# UI_Adapter_SMD.net
KiCad netlist of a schematic drawn in EAGLE
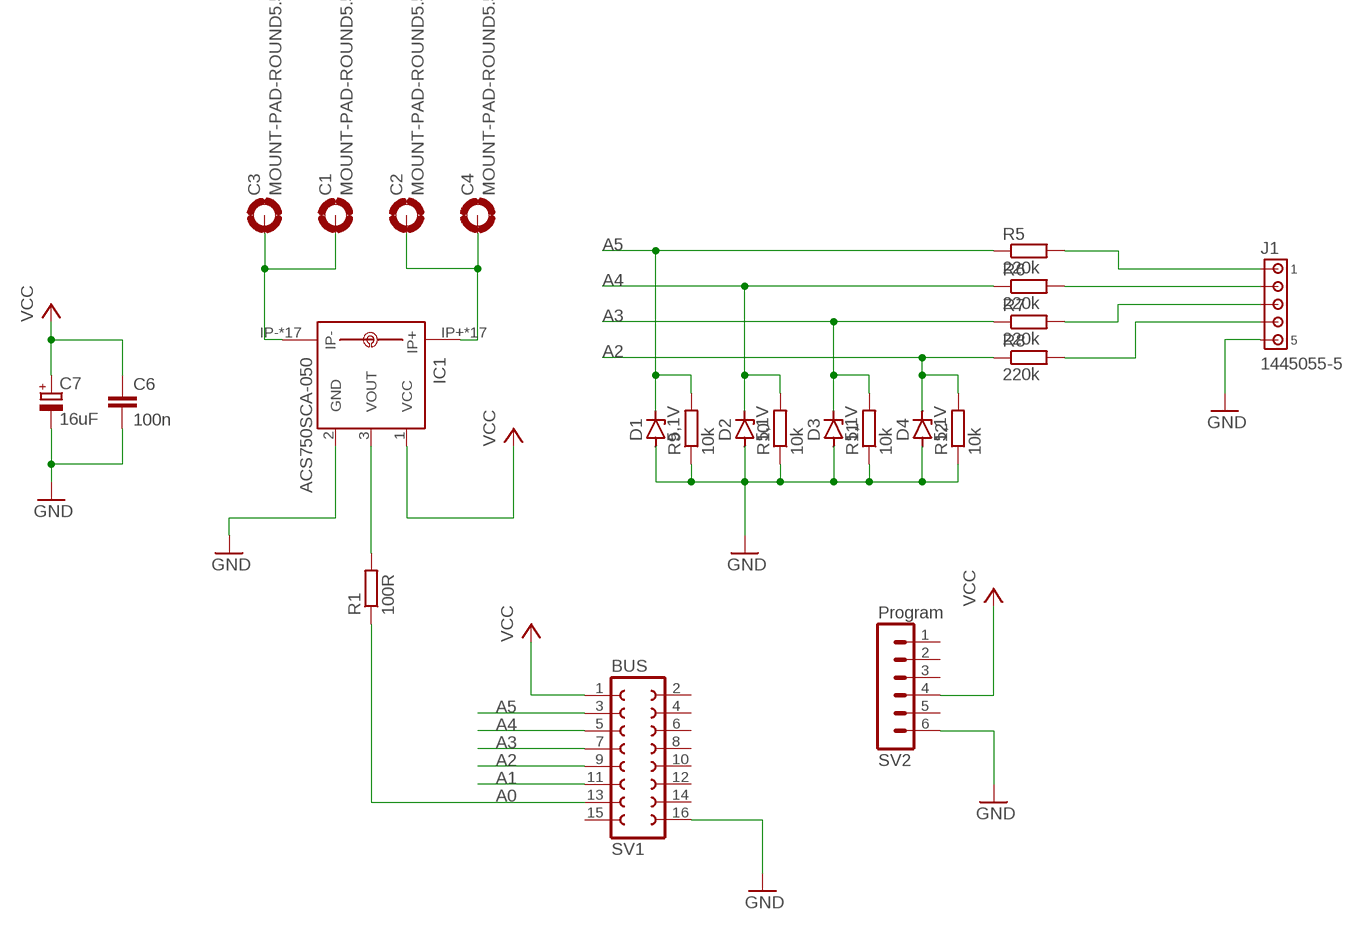
[diagram p0: schematic, sheet 1]

(export (version "E")
  (design (tool "Eeschema 10.0.6"))
  (components
    (comp (ref "C1")
      (value "MOUNT-PAD-ROUND5.5")
      (footprint "eagle-import:5,5-PAD")
      (libsource (lib "eagle-import") (part "MOUNT-PAD-ROUND5.5"))
    )
    (comp (ref "C2")
      (value "MOUNT-PAD-ROUND5.5")
      (footprint "eagle-import:5,5-PAD")
      (libsource (lib "eagle-import") (part "MOUNT-PAD-ROUND5.5"))
    )
    (comp (ref "C3")
      (value "MOUNT-PAD-ROUND5.5")
      (footprint "eagle-import:5,5-PAD")
      (libsource (lib "eagle-import") (part "MOUNT-PAD-ROUND5.5"))
    )
    (comp (ref "C4")
      (value "MOUNT-PAD-ROUND5.5")
      (footprint "eagle-import:5,5-PAD")
      (libsource (lib "eagle-import") (part "MOUNT-PAD-ROUND5.5"))
    )
    (comp (ref "C6")
      (value "100n")
      (footprint "eagle-import:C0402K")
      (libsource (lib "eagle-import") (part "C-EUC0402K"))
    )
    (comp (ref "C7")
      (value "16uF")
      (footprint "eagle-import:A_3216-18W")
      (libsource (lib "eagle-import") (part "CPOL-EUA/3216-18W"))
    )
    (comp (ref "D1")
      (value "5,1V")
      (footprint "eagle-import:SOD80C")
      (libsource (lib "eagle-import") (part "ZENER-DIODESOD80C"))
    )
    (comp (ref "D2")
      (value "5,1V")
      (footprint "eagle-import:SOD80C")
      (libsource (lib "eagle-import") (part "ZENER-DIODESOD80C"))
    )
    (comp (ref "D3")
      (value "5,1V")
      (footprint "eagle-import:SOD80C")
      (libsource (lib "eagle-import") (part "ZENER-DIODESOD80C"))
    )
    (comp (ref "D4")
      (value "5,1V")
      (footprint "eagle-import:SOD80C")
      (libsource (lib "eagle-import") (part "ZENER-DIODESOD80C"))
    )
    (comp (ref "IC1")
      (value "ACS750SCA-050")
      (footprint "eagle-import:ACS75050")
      (fields (field (name "MF") "ALLEGRO MICROSYSTEMS, INC."))
      (libsource (lib "eagle-import") (part "ACS750CA-050S"))
    )
    (comp (ref "J1")
      (value "1445055-5")
      (footprint "eagle-import:1445055-5")
      (libsource (lib "eagle-import") (part "1445055-5"))
    )
    (comp (ref "R1")
      (value "100R")
      (footprint "eagle-import:R0402")
      (libsource (lib "eagle-import") (part "R-EU_R0402"))
    )
    (comp (ref "R5")
      (value "220k")
      (footprint "eagle-import:R0402")
      (libsource (lib "eagle-import") (part "R-EU_R0402"))
    )
    (comp (ref "R6")
      (value "220k")
      (footprint "eagle-import:R0402")
      (libsource (lib "eagle-import") (part "R-EU_R0402"))
    )
    (comp (ref "R7")
      (value "220k")
      (footprint "eagle-import:R0402")
      (libsource (lib "eagle-import") (part "R-EU_R0402"))
    )
    (comp (ref "R8")
      (value "220k")
      (footprint "eagle-import:R0402")
      (libsource (lib "eagle-import") (part "R-EU_R0402"))
    )
    (comp (ref "R9")
      (value "10k")
      (footprint "eagle-import:R0402")
      (libsource (lib "eagle-import") (part "R-EU_R0402"))
    )
    (comp (ref "R10")
      (value "10k")
      (footprint "eagle-import:R0402")
      (libsource (lib "eagle-import") (part "R-EU_R0402"))
    )
    (comp (ref "R11")
      (value "10k")
      (footprint "eagle-import:R0402")
      (libsource (lib "eagle-import") (part "R-EU_R0402"))
    )
    (comp (ref "R12")
      (value "10k")
      (footprint "eagle-import:R0402")
      (libsource (lib "eagle-import") (part "R-EU_R0402"))
    )
    (comp (ref "SV1")
      (value "BUS")
      (footprint "eagle-import:FE08-2")
      (libsource (lib "eagle-import") (part "FE08-2"))
    )
    (comp (ref "SV2")
      (value "Program")
      (footprint "eagle-import:MA06-1")
      (libsource (lib "eagle-import") (part "MA06-1"))
    )
  )
  (nets
    (net (code "1") (name "A0") (class "Default")
      (node (ref "R1") (pin "1") (pinfunction "1_1") (pintype "passive"))
      (node (ref "SV1") (pin "13") (pinfunction "13_13") (pintype "passive"))
    )
    (net (code "2") (name "A1") (class "Default")
      (node (ref "SV1") (pin "11") (pinfunction "11_11") (pintype "passive"))
    )
    (net (code "3") (name "A2") (class "Default")
      (node (ref "D4") (pin "C") (pinfunction "C_C") (pintype "passive"))
      (node (ref "R12") (pin "2") (pinfunction "2_2") (pintype "passive"))
      (node (ref "R8") (pin "1") (pinfunction "1_1") (pintype "passive"))
      (node (ref "SV1") (pin "9") (pinfunction "9_9") (pintype "passive"))
    )
    (net (code "4") (name "A3") (class "Default")
      (node (ref "D3") (pin "C") (pinfunction "C_C") (pintype "passive"))
      (node (ref "R11") (pin "2") (pinfunction "2_2") (pintype "passive"))
      (node (ref "R7") (pin "1") (pinfunction "1_1") (pintype "passive"))
      (node (ref "SV1") (pin "7") (pinfunction "7_7") (pintype "passive"))
    )
    (net (code "5") (name "A4") (class "Default")
      (node (ref "D2") (pin "C") (pinfunction "C_C") (pintype "passive"))
      (node (ref "R10") (pin "2") (pinfunction "2_2") (pintype "passive"))
      (node (ref "R6") (pin "1") (pinfunction "1_1") (pintype "passive"))
      (node (ref "SV1") (pin "5") (pinfunction "5_5") (pintype "passive"))
    )
    (net (code "6") (name "A5") (class "Default")
      (node (ref "D1") (pin "C") (pinfunction "C_C") (pintype "passive"))
      (node (ref "R5") (pin "1") (pinfunction "1_1") (pintype "passive"))
      (node (ref "R9") (pin "2") (pinfunction "2_2") (pintype "passive"))
      (node (ref "SV1") (pin "3") (pinfunction "3_3") (pintype "passive"))
    )
    (net (code "7") (name "GND") (class "Default")
      (node (ref "C6") (pin "2") (pinfunction "2_2") (pintype "passive"))
      (node (ref "C7") (pin "-") (pinfunction "-_-") (pintype "passive"))
      (node (ref "D1") (pin "A") (pinfunction "A_A") (pintype "passive"))
      (node (ref "D2") (pin "A") (pinfunction "A_A") (pintype "passive"))
      (node (ref "D3") (pin "A") (pinfunction "A_A") (pintype "passive"))
      (node (ref "D4") (pin "A") (pinfunction "A_A") (pintype "passive"))
      (node (ref "IC1") (pin "2") (pinfunction "GND_2") (pintype "power_in"))
      (node (ref "J1") (pin "5") (pinfunction "5_5") (pintype "passive"))
      (node (ref "R10") (pin "1") (pinfunction "1_1") (pintype "passive"))
      (node (ref "R11") (pin "1") (pinfunction "1_1") (pintype "passive"))
      (node (ref "R12") (pin "1") (pinfunction "1_1") (pintype "passive"))
      (node (ref "R9") (pin "1") (pinfunction "1_1") (pintype "passive"))
      (node (ref "SV1") (pin "16") (pinfunction "16_16") (pintype "passive"))
      (node (ref "SV2") (pin "6") (pinfunction "6_6") (pintype "passive"))
    )
    (net (code "8") (name "Net-(C1-MOUNT)") (class "Default")
      (node (ref "C1") (pin "B5,5") (pinfunction "MOUNT_B5,5") (pintype "passive"))
      (node (ref "C3") (pin "B5,5") (pinfunction "MOUNT_B5,5") (pintype "passive"))
      (node (ref "IC1") (pin "IP-") (pinfunction "IP-_IP-") (pintype "passive"))
      (node (ref "IC1") (pin "IP-@10") (pinfunction "IP-_IP-@10") (pintype "passive"))
      (node (ref "IC1") (pin "IP-@11") (pinfunction "IP-_IP-@11") (pintype "passive"))
      (node (ref "IC1") (pin "IP-@12") (pinfunction "IP-_IP-@12") (pintype "passive"))
      (node (ref "IC1") (pin "IP-@13") (pinfunction "IP-_IP-@13") (pintype "passive"))
      (node (ref "IC1") (pin "IP-@14") (pinfunction "IP-_IP-@14") (pintype "passive"))
      (node (ref "IC1") (pin "IP-@15") (pinfunction "IP-_IP-@15") (pintype "passive"))
      (node (ref "IC1") (pin "IP-@16") (pinfunction "IP-_IP-@16") (pintype "passive"))
      (node (ref "IC1") (pin "IP-@17") (pinfunction "IP-_IP-@17") (pintype "passive"))
      (node (ref "IC1") (pin "IP-@2") (pinfunction "IP-_IP-@2") (pintype "passive"))
      (node (ref "IC1") (pin "IP-@3") (pinfunction "IP-_IP-@3") (pintype "passive"))
      (node (ref "IC1") (pin "IP-@4") (pinfunction "IP-_IP-@4") (pintype "passive"))
      (node (ref "IC1") (pin "IP-@5") (pinfunction "IP-_IP-@5") (pintype "passive"))
      (node (ref "IC1") (pin "IP-@6") (pinfunction "IP-_IP-@6") (pintype "passive"))
      (node (ref "IC1") (pin "IP-@7") (pinfunction "IP-_IP-@7") (pintype "passive"))
      (node (ref "IC1") (pin "IP-@8") (pinfunction "IP-_IP-@8") (pintype "passive"))
      (node (ref "IC1") (pin "IP-@9") (pinfunction "IP-_IP-@9") (pintype "passive"))
    )
    (net (code "9") (name "Net-(C2-MOUNT)") (class "Default")
      (node (ref "C2") (pin "B5,5") (pinfunction "MOUNT_B5,5") (pintype "passive"))
      (node (ref "C4") (pin "B5,5") (pinfunction "MOUNT_B5,5") (pintype "passive"))
      (node (ref "IC1") (pin "IP+") (pinfunction "IP+_IP+") (pintype "passive"))
      (node (ref "IC1") (pin "IP+@10") (pinfunction "IP+_IP+@10") (pintype "passive"))
      (node (ref "IC1") (pin "IP+@11") (pinfunction "IP+_IP+@11") (pintype "passive"))
      (node (ref "IC1") (pin "IP+@12") (pinfunction "IP+_IP+@12") (pintype "passive"))
      (node (ref "IC1") (pin "IP+@13") (pinfunction "IP+_IP+@13") (pintype "passive"))
      (node (ref "IC1") (pin "IP+@14") (pinfunction "IP+_IP+@14") (pintype "passive"))
      (node (ref "IC1") (pin "IP+@15") (pinfunction "IP+_IP+@15") (pintype "passive"))
      (node (ref "IC1") (pin "IP+@16") (pinfunction "IP+_IP+@16") (pintype "passive"))
      (node (ref "IC1") (pin "IP+@17") (pinfunction "IP+_IP+@17") (pintype "passive"))
      (node (ref "IC1") (pin "IP+@2") (pinfunction "IP+_IP+@2") (pintype "passive"))
      (node (ref "IC1") (pin "IP+@3") (pinfunction "IP+_IP+@3") (pintype "passive"))
      (node (ref "IC1") (pin "IP+@4") (pinfunction "IP+_IP+@4") (pintype "passive"))
      (node (ref "IC1") (pin "IP+@5") (pinfunction "IP+_IP+@5") (pintype "passive"))
      (node (ref "IC1") (pin "IP+@6") (pinfunction "IP+_IP+@6") (pintype "passive"))
      (node (ref "IC1") (pin "IP+@7") (pinfunction "IP+_IP+@7") (pintype "passive"))
      (node (ref "IC1") (pin "IP+@8") (pinfunction "IP+_IP+@8") (pintype "passive"))
      (node (ref "IC1") (pin "IP+@9") (pinfunction "IP+_IP+@9") (pintype "passive"))
    )
    (net (code "10") (name "Net-(IC1-VOUT)") (class "Default")
      (node (ref "IC1") (pin "3") (pinfunction "VOUT_3") (pintype "output"))
      (node (ref "R1") (pin "2") (pinfunction "2_2") (pintype "passive"))
    )
    (net (code "11") (name "Net-(J1-Pad1)") (class "Default")
      (node (ref "J1") (pin "1") (pinfunction "1_1") (pintype "passive"))
      (node (ref "R5") (pin "2") (pinfunction "2_2") (pintype "passive"))
    )
    (net (code "12") (name "Net-(J1-Pad2)") (class "Default")
      (node (ref "J1") (pin "2") (pinfunction "2_2") (pintype "passive"))
      (node (ref "R6") (pin "2") (pinfunction "2_2") (pintype "passive"))
    )
    (net (code "13") (name "Net-(J1-Pad3)") (class "Default")
      (node (ref "J1") (pin "3") (pinfunction "3_3") (pintype "passive"))
      (node (ref "R7") (pin "2") (pinfunction "2_2") (pintype "passive"))
    )
    (net (code "14") (name "Net-(J1-Pad4)") (class "Default")
      (node (ref "J1") (pin "4") (pinfunction "4_4") (pintype "passive"))
      (node (ref "R8") (pin "2") (pinfunction "2_2") (pintype "passive"))
    )
    (net (code "15") (name "VCC") (class "Default")
      (node (ref "C6") (pin "1") (pinfunction "1_1") (pintype "passive"))
      (node (ref "C7") (pin "+") (pinfunction "+_+") (pintype "passive"))
      (node (ref "IC1") (pin "1") (pinfunction "VCC_1") (pintype "power_in"))
      (node (ref "SV1") (pin "1") (pinfunction "1_1") (pintype "passive"))
      (node (ref "SV2") (pin "4") (pinfunction "4_4") (pintype "passive"))
    )
    (net (code "16") (name "unconnected-(SV1-Pad2)") (class "Default")
      (node (ref "SV1") (pin "2") (pinfunction "2_2") (pintype "passive"))
    )
    (net (code "17") (name "unconnected-(SV1-Pad4)") (class "Default")
      (node (ref "SV1") (pin "4") (pinfunction "4_4") (pintype "passive"))
    )
    (net (code "18") (name "unconnected-(SV1-Pad6)") (class "Default")
      (node (ref "SV1") (pin "6") (pinfunction "6_6") (pintype "passive"))
    )
    (net (code "19") (name "unconnected-(SV1-Pad8)") (class "Default")
      (node (ref "SV1") (pin "8") (pinfunction "8_8") (pintype "passive"))
    )
    (net (code "20") (name "unconnected-(SV1-Pad10)") (class "Default")
      (node (ref "SV1") (pin "10") (pinfunction "10_10") (pintype "passive"))
    )
    (net (code "21") (name "unconnected-(SV1-Pad12)") (class "Default")
      (node (ref "SV1") (pin "12") (pinfunction "12_12") (pintype "passive"))
    )
    (net (code "22") (name "unconnected-(SV1-Pad14)") (class "Default")
      (node (ref "SV1") (pin "14") (pinfunction "14_14") (pintype "passive"))
    )
    (net (code "23") (name "unconnected-(SV1-Pad15)") (class "Default")
      (node (ref "SV1") (pin "15") (pinfunction "15_15") (pintype "passive"))
    )
    (net (code "24") (name "unconnected-(SV2-Pad1)") (class "Default")
      (node (ref "SV2") (pin "1") (pinfunction "1_1") (pintype "passive"))
    )
    (net (code "25") (name "unconnected-(SV2-Pad2)") (class "Default")
      (node (ref "SV2") (pin "2") (pinfunction "2_2") (pintype "passive"))
    )
    (net (code "26") (name "unconnected-(SV2-Pad3)") (class "Default")
      (node (ref "SV2") (pin "3") (pinfunction "3_3") (pintype "passive"))
    )
    (net (code "27") (name "unconnected-(SV2-Pad5)") (class "Default")
      (node (ref "SV2") (pin "5") (pinfunction "5_5") (pintype "passive"))
    )
  )
)
